# PLL_schematics.net
KiCad netlist of a schematic drawn in EAGLE
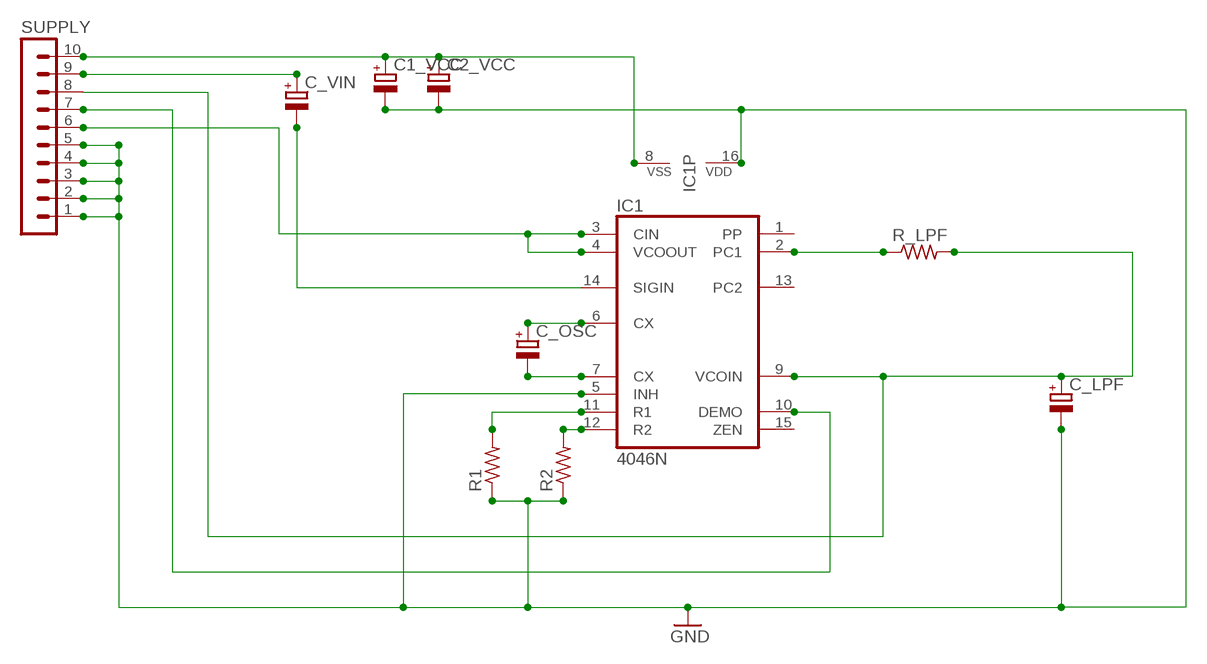
[diagram p0: schematic, sheet 1]

(export (version "E")
  (design (tool "Eeschema 10.0.6"))
  (components
    (comp (ref "C1_VCC")
      (value "CPOL-EUTAP5-50")
      (footprint "eagle-import:TAP5-50")
      (libsource (lib "eagle-import") (part "CPOL-EUTAP5-50"))
    )
    (comp (ref "C2_VCC")
      (value "CPOL-EUTAP5-50")
      (footprint "eagle-import:TAP5-50")
      (libsource (lib "eagle-import") (part "CPOL-EUTAP5-50"))
    )
    (comp (ref "C_LPF")
      (value "CPOL-EUTAP5-50")
      (footprint "eagle-import:TAP5-50")
      (libsource (lib "eagle-import") (part "CPOL-EUTAP5-50"))
    )
    (comp (ref "C_OSC")
      (value "CPOL-EUTAP5-50")
      (footprint "eagle-import:TAP5-50")
      (libsource (lib "eagle-import") (part "CPOL-EUTAP5-50"))
    )
    (comp (ref "C_VIN")
      (value "CPOL-EUTAP5-50")
      (footprint "eagle-import:TAP5-50")
      (libsource (lib "eagle-import") (part "CPOL-EUTAP5-50"))
    )
    (comp (ref "IC1")
      (value "4046N")
      (footprint "eagle-import:DIL16")
      (libsource (lib "eagle-import") (part "4046N"))
    )
    (comp (ref "R1")
      (value "R-US_0207/12")
      (footprint "eagle-import:0207_12")
      (libsource (lib "eagle-import") (part "R-US_0207/12"))
    )
    (comp (ref "R2")
      (value "R-US_0207/12")
      (footprint "eagle-import:0207_12")
      (libsource (lib "eagle-import") (part "R-US_0207/12"))
    )
    (comp (ref "R_LPF")
      (value "R-US_0207/12")
      (footprint "eagle-import:0207_12")
      (libsource (lib "eagle-import") (part "R-US_0207/12"))
    )
    (comp (ref "SUPPLY")
      (value "MA10-1")
      (footprint "eagle-import:MA10-1")
      (libsource (lib "eagle-import") (part "MA10-1"))
    )
  )
  (nets
    (net (code "1") (name "GND") (class "Default")
      (node (ref "C1_VCC") (pin "-") (pinfunction "-_-") (pintype "passive"))
      (node (ref "C2_VCC") (pin "-") (pinfunction "-_-") (pintype "passive"))
      (node (ref "C_LPF") (pin "-") (pinfunction "-_-") (pintype "passive"))
      (node (ref "IC1") (pin "16") (pinfunction "VDD_16") (pintype "power_in"))
      (node (ref "IC1") (pin "5") (pinfunction "INH_5") (pintype "input"))
      (node (ref "R1") (pin "1") (pinfunction "1_1") (pintype "passive"))
      (node (ref "R2") (pin "1") (pinfunction "1_1") (pintype "passive"))
      (node (ref "SUPPLY") (pin "1") (pinfunction "1_1") (pintype "passive"))
      (node (ref "SUPPLY") (pin "2") (pinfunction "2_2") (pintype "passive"))
      (node (ref "SUPPLY") (pin "3") (pinfunction "3_3") (pintype "passive"))
      (node (ref "SUPPLY") (pin "4") (pinfunction "4_4") (pintype "passive"))
      (node (ref "SUPPLY") (pin "5") (pinfunction "5_5") (pintype "passive"))
    )
    (net (code "2") (name "Net-(C_OSC-Pad+)") (class "Default")
      (node (ref "C_OSC") (pin "+") (pinfunction "+_+") (pintype "passive"))
      (node (ref "IC1") (pin "6") (pinfunction "CX_6") (pintype "input"))
    )
    (net (code "3") (name "Net-(C_OSC-Pad-)") (class "Default")
      (node (ref "C_OSC") (pin "-") (pinfunction "-_-") (pintype "passive"))
      (node (ref "IC1") (pin "7") (pinfunction "CX_7") (pintype "input"))
    )
    (net (code "4") (name "Net-(C_VIN-Pad+)") (class "Default")
      (node (ref "C_VIN") (pin "+") (pinfunction "+_+") (pintype "passive"))
      (node (ref "SUPPLY") (pin "9") (pinfunction "9_9") (pintype "passive"))
    )
    (net (code "5") (name "Net-(IC1A-CIN)") (class "Default")
      (node (ref "IC1") (pin "3") (pinfunction "CIN_3") (pintype "input"))
      (node (ref "IC1") (pin "4") (pinfunction "VCOOUT_4") (pintype "output"))
      (node (ref "SUPPLY") (pin "6") (pinfunction "6_6") (pintype "passive"))
    )
    (net (code "6") (name "Net-(IC1A-DEMO)") (class "Default")
      (node (ref "IC1") (pin "10") (pinfunction "DEMO_10") (pintype "output"))
      (node (ref "SUPPLY") (pin "7") (pinfunction "7_7") (pintype "passive"))
    )
    (net (code "7") (name "Net-(IC1A-PC1)") (class "Default")
      (node (ref "IC1") (pin "2") (pinfunction "PC1_2") (pintype "output"))
      (node (ref "R_LPF") (pin "1") (pinfunction "1_1") (pintype "passive"))
    )
    (net (code "8") (name "Net-(IC1A-R1)") (class "Default")
      (node (ref "IC1") (pin "11") (pinfunction "R1_11") (pintype "input"))
      (node (ref "R1") (pin "2") (pinfunction "2_2") (pintype "passive"))
    )
    (net (code "9") (name "Net-(IC1A-R2)") (class "Default")
      (node (ref "IC1") (pin "12") (pinfunction "R2_12") (pintype "input"))
      (node (ref "R2") (pin "2") (pinfunction "2_2") (pintype "passive"))
    )
    (net (code "10") (name "Net-(IC1A-SIGIN)") (class "Default")
      (node (ref "C_VIN") (pin "-") (pinfunction "-_-") (pintype "passive"))
      (node (ref "IC1") (pin "14") (pinfunction "SIGIN_14") (pintype "input"))
    )
    (net (code "11") (name "Net-(IC1A-VCOIN)") (class "Default")
      (node (ref "C_LPF") (pin "+") (pinfunction "+_+") (pintype "passive"))
      (node (ref "IC1") (pin "9") (pinfunction "VCOIN_9") (pintype "input"))
      (node (ref "R_LPF") (pin "2") (pinfunction "2_2") (pintype "passive"))
      (node (ref "SUPPLY") (pin "8") (pinfunction "8_8") (pintype "passive"))
    )
    (net (code "12") (name "Net-(IC1B-VSS)") (class "Default")
      (node (ref "C1_VCC") (pin "+") (pinfunction "+_+") (pintype "passive"))
      (node (ref "C2_VCC") (pin "+") (pinfunction "+_+") (pintype "passive"))
      (node (ref "IC1") (pin "8") (pinfunction "VSS_8") (pintype "power_in"))
      (node (ref "SUPPLY") (pin "10") (pinfunction "10_10") (pintype "passive"))
    )
    (net (code "13") (name "unconnected-(IC1A-PC2-Pad13)") (class "Default")
      (node (ref "IC1") (pin "13") (pinfunction "PC2_13") (pintype "output"))
    )
    (net (code "14") (name "unconnected-(IC1A-PP-Pad1)") (class "Default")
      (node (ref "IC1") (pin "1") (pinfunction "PP_1") (pintype "output"))
    )
    (net (code "15") (name "unconnected-(IC1A-ZEN-Pad15)") (class "Default")
      (node (ref "IC1") (pin "15") (pinfunction "ZEN_15") (pintype "input"))
    )
  )
)
